# ttl_logic_mech.net
KiCad netlist of a schematic drawn in Altium Designer
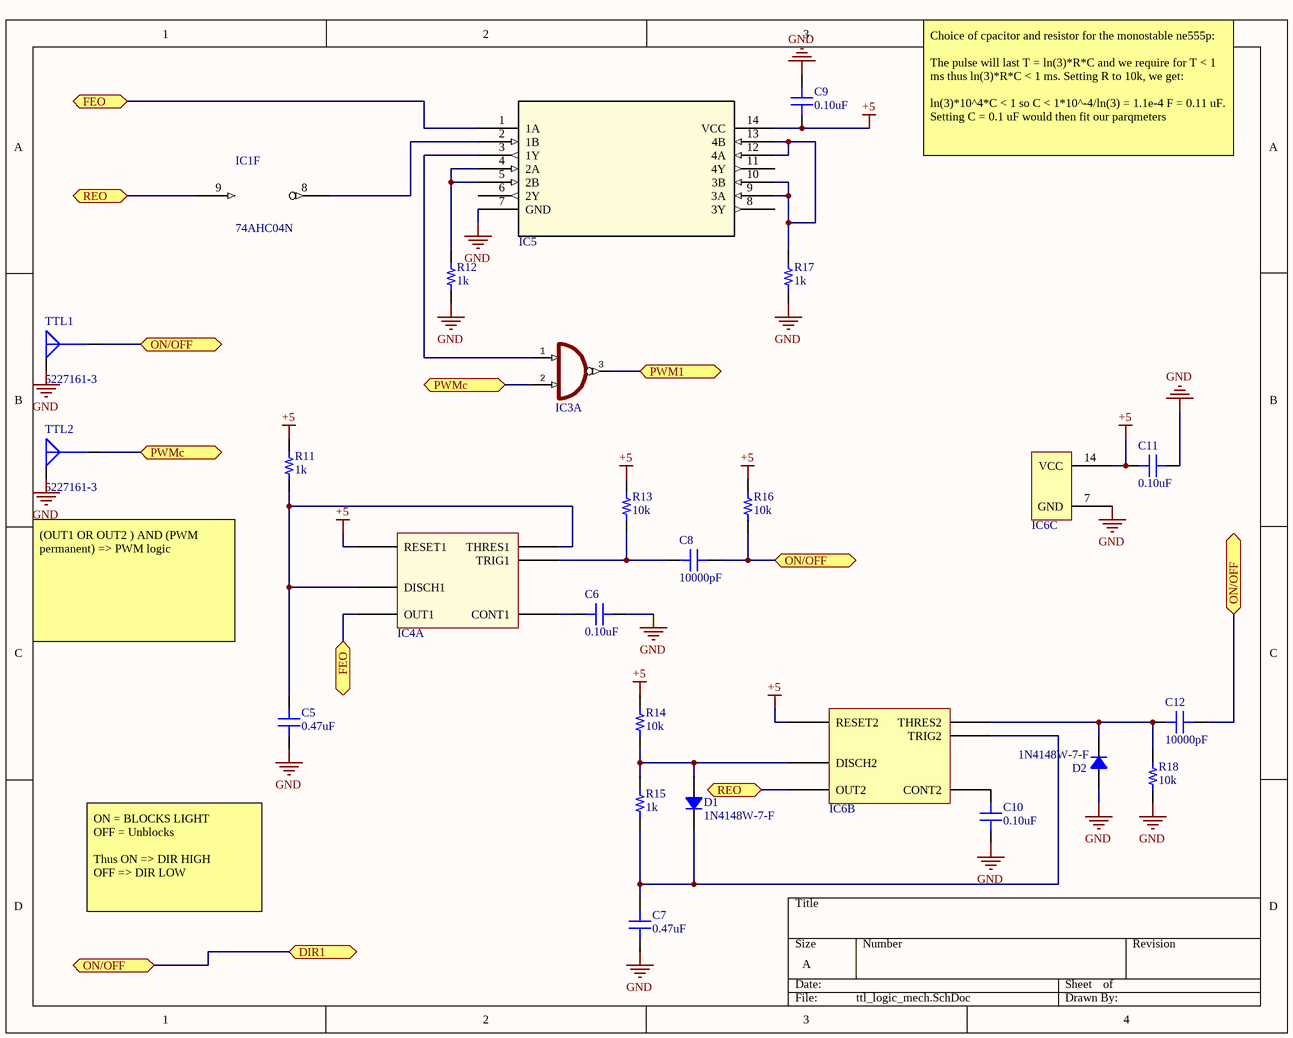
[diagram p0: ttl_logic_mech.SchDoc]

(export (version "E")
  (design (tool "Eeschema 10.0.6"))
  (components
    (comp (ref "C5")
      (value "0.47uF")
      (footprint "CAP 0805/2012")
      (description "CAP CER 0.47UF 16V X7R 0805")
      (fields (field (name "PART NUMBER") "C0805C474J4RACTU") (field (name "MANUFACTURER") "Kemet"))
      (libsource (lib "Celestial Library Database") (part "Capacitor"))
    )
    (comp (ref "C6")
      (value "0.10uF")
      (footprint "CAP 1206/3216 - 1.0MM")
      (description "CAP CER 0.1UF 16V X7R 1206")
      (fields (field (name "PART NUMBER") "C1206C104K4RACTU") (field (name "MANUFACTURER") "Kemet"))
      (libsource (lib "Celestial Library Database") (part "Capacitor"))
    )
    (comp (ref "C7")
      (value "0.47uF")
      (footprint "CAP 0805/2012")
      (description "CAP CER 0.47UF 16V X7R 0805")
      (fields (field (name "PART NUMBER") "C0805C474J4RACTU") (field (name "MANUFACTURER") "Kemet"))
      (libsource (lib "Celestial Library Database") (part "Capacitor"))
    )
    (comp (ref "C8")
      (value "10000pF")
      (footprint "CAP 0805/2012")
      (description "CAP CER 10000PF 25V X7R 0805")
      (fields (field (name "PART NUMBER") "C0805C103J3RACTU") (field (name "MANUFACTURER") "Kemet"))
      (libsource (lib "Celestial Library Database") (part "Capacitor"))
    )
    (comp (ref "C9")
      (value "0.10uF")
      (footprint "CAP 1206/3216 - 1.0MM")
      (description "CAP CER 0.1UF 16V X7R 1206")
      (fields (field (name "PART NUMBER") "C1206C104K4RACTU") (field (name "MANUFACTURER") "Kemet"))
      (libsource (lib "Celestial Library Database") (part "Capacitor"))
    )
    (comp (ref "C10")
      (value "0.10uF")
      (footprint "CAP 1206/3216 - 1.0MM")
      (description "CAP CER 0.1UF 16V X7R 1206")
      (fields (field (name "PART NUMBER") "C1206C104K4RACTU") (field (name "MANUFACTURER") "Kemet"))
      (libsource (lib "Celestial Library Database") (part "Capacitor"))
    )
    (comp (ref "C11")
      (value "0.10uF")
      (footprint "CAP 1206/3216 - 1.0MM")
      (description "CAP CER 0.1UF 16V X7R 1206")
      (fields (field (name "PART NUMBER") "C1206C104K4RACTU") (field (name "MANUFACTURER") "Kemet"))
      (libsource (lib "Celestial Library Database") (part "Capacitor"))
    )
    (comp (ref "C12")
      (value "10000pF")
      (footprint "CAP 0805/2012")
      (description "CAP CER 10000PF 25V X7R 0805")
      (fields (field (name "PART NUMBER") "C0805C103J3RACTU") (field (name "MANUFACTURER") "Kemet"))
      (libsource (lib "Celestial Library Database") (part "Capacitor"))
    )
    (comp (ref "D1")
      (value "1N4148W-7-F")
      (footprint "SOD-123")
      (description "DIODE GEN PURP 100V 300MA SOD123")
      (fields (field (name "MANUFACTURER") "Diodes Incorporated"))
      (libsource (lib "Celestial Library Database") (part "Diode"))
    )
    (comp (ref "D2")
      (value "1N4148W-7-F")
      (footprint "SOD-123")
      (description "DIODE GEN PURP 100V 300MA SOD123")
      (fields (field (name "MANUFACTURER") "Diodes Incorporated"))
      (libsource (lib "Celestial Library Database") (part "Diode"))
    )
    (comp (ref "IC1") (value "74AHC04N") (footprint "DIL14") (libsource (lib "74ac-logic") (part "74AHC04N")))
    (comp (ref "IC3")
      (value "~")
      (footprint "Atmel SO-14 14S1")
      (description "IC GATE AND 4CH 2-INP 14-SOIC")
      (fields (field (name "PART NUMBER") "SN74AC08D") (field (name "MANUFACTURER") "Texas Instruments"))
      (libsource (lib "Celestial Library Database") (part "74AC08N"))
    )
    (comp (ref "IC4")
      (value "NE556D")
      (footprint "Atmel SO-14 14S1")
      (description "2 ne555 timers in one soic 14")
      (fields (field (name "MANUFACTURER") "Texas Instruments"))
      (libsource (lib "Celestial Library Database") (part "NE556P"))
    )
    (comp (ref "IC5")
      (value "SN74LS86ADR")
      (footprint "Atmel SO-14 14S1")
      (description "IC GATE XOR 4CH 2-INP 14-SOIC")
      (fields (field (name "MANUFACTURER") "Texas Instruments"))
      (libsource (lib "Celestial Library Database") (part "SN74LS86ADR"))
    )
    (comp (ref "IC6")
      (value "NE556P")
      (footprint "DIP14")
      (fields (field (name "MANUFACTURER") "Texas Instruments"))
      (libsource (lib "Celestial Library Database") (part "NE556P"))
    )
    (comp (ref "R11")
      (value "1k")
      (footprint "RES 1206/3216")
      (description "RES SMD 1K OHM 0.05% 1/4W 1206")
      (fields
        (field (name "PART NUMBER") "ERA-8ARW102V")
        (field (name "MANUFACTURER") "Panasonic Electronic Components")
      )
      (libsource (lib "Celestial Library Database") (part "Resistor"))
    )
    (comp (ref "R12")
      (value "1k")
      (footprint "RES 1206/3216")
      (description "RES SMD 1K OHM 0.05% 1/4W 1206")
      (fields
        (field (name "PART NUMBER") "ERA-8ARW102V")
        (field (name "MANUFACTURER") "Panasonic Electronic Components")
      )
      (libsource (lib "Celestial Library Database") (part "Resistor"))
    )
    (comp (ref "R13")
      (value "10k")
      (footprint "RES 1206/3216")
      (description "RES SMD 10K OHM 5% 1/4W 1206")
      (fields
        (field (name "PART NUMBER") "ERJ-8GEYJ103V")
        (field (name "MANUFACTURER") "Panasonic Electronic Components")
      )
      (libsource (lib "Celestial Library Database") (part "Resistor"))
    )
    (comp (ref "R14")
      (value "10k")
      (footprint "RES 1206/3216")
      (description "RES SMD 10K OHM 5% 1/4W 1206")
      (fields
        (field (name "PART NUMBER") "ERJ-8GEYJ103V")
        (field (name "MANUFACTURER") "Panasonic Electronic Components")
      )
      (libsource (lib "Celestial Library Database") (part "Resistor"))
    )
    (comp (ref "R15")
      (value "1k")
      (footprint "RES 1206/3216")
      (description "RES SMD 1K OHM 0.05% 1/4W 1206")
      (fields
        (field (name "PART NUMBER") "ERA-8ARW102V")
        (field (name "MANUFACTURER") "Panasonic Electronic Components")
      )
      (libsource (lib "Celestial Library Database") (part "Resistor"))
    )
    (comp (ref "R16")
      (value "10k")
      (footprint "RES 1206/3216")
      (description "RES SMD 10K OHM 5% 1/4W 1206")
      (fields
        (field (name "PART NUMBER") "ERJ-8GEYJ103V")
        (field (name "MANUFACTURER") "Panasonic Electronic Components")
      )
      (libsource (lib "Celestial Library Database") (part "Resistor"))
    )
    (comp (ref "R17")
      (value "1k")
      (footprint "RES 1206/3216")
      (description "RES SMD 1K OHM 0.05% 1/4W 1206")
      (fields
        (field (name "PART NUMBER") "ERA-8ARW102V")
        (field (name "MANUFACTURER") "Panasonic Electronic Components")
      )
      (libsource (lib "Celestial Library Database") (part "Resistor"))
    )
    (comp (ref "R18")
      (value "10k")
      (footprint "RES 1206/3216")
      (description "RES SMD 10K OHM 5% 1/4W 1206")
      (fields
        (field (name "PART NUMBER") "ERJ-8GEYJ103V")
        (field (name "MANUFACTURER") "Panasonic Electronic Components")
      )
      (libsource (lib "Celestial Library Database") (part "Resistor"))
    )
    (comp (ref "TTL1")
      (value "5227161-3")
      (footprint "5227161-3")
      (description "CONN BNC JACK R/A 50 OHM PCB")
      (fields (field (name "MANUFACTURER") "TE Connectivity AMP Connectors"))
      (libsource (lib "Celestial Library Database") (part "RF Connector - SMA"))
    )
    (comp (ref "TTL2")
      (value "5227161-3")
      (footprint "5227161-3")
      (description "CONN BNC JACK R/A 50 OHM PCB")
      (fields (field (name "MANUFACTURER") "TE Connectivity AMP Connectors"))
      (libsource (lib "Celestial Library Database") (part "RF Connector - SMA"))
    )
  )
  (nets
    (net (code "1") (name "+5") (class "Default")
      (node (ref "C11") (pin "2") (pinfunction "2_2") (pintype "passive"))
      (node (ref "C9") (pin "2") (pinfunction "2_2") (pintype "passive"))
      (node (ref "IC4") (pin "4") (pinfunction "RESET1_4") (pintype "passive"))
      (node (ref "IC5") (pin "14") (pinfunction "VCC_14") (pintype "power_in"))
      (node (ref "IC6") (pin "10") (pinfunction "RESET2_10") (pintype "passive"))
      (node (ref "IC6") (pin "14") (pinfunction "VCC_14") (pintype "passive"))
      (node (ref "R11") (pin "2") (pinfunction "2_2") (pintype "passive"))
      (node (ref "R13") (pin "2") (pinfunction "2_2") (pintype "passive"))
      (node (ref "R14") (pin "2") (pinfunction "2_2") (pintype "passive"))
      (node (ref "R16") (pin "2") (pinfunction "2_2") (pintype "passive"))
    )
    (net (code "2") (name "/DIR1") (class "Default")
      (node (ref "C12") (pin "2") (pinfunction "2_2") (pintype "passive"))
      (node (ref "C8") (pin "2") (pinfunction "2_2") (pintype "passive"))
      (node (ref "R16") (pin "1") (pinfunction "1_1") (pintype "passive"))
      (node (ref "TTL1") (pin "S") (pinfunction "S_S") (pintype "passive"))
    )
    (net (code "3") (name "/FEO") (class "Default")
      (node (ref "IC4") (pin "5") (pinfunction "OUT1_5") (pintype "passive"))
      (node (ref "IC5") (pin "1") (pinfunction "1A_1") (pintype "power_in"))
    )
    (net (code "4") (name "/PWM1") (class "Default")
      (node (ref "IC3") (pin "3") (pinfunction "O_3") (pintype "output"))
    )
    (net (code "5") (name "/PWMc") (class "Default")
      (node (ref "IC3") (pin "2") (pinfunction "I1_2") (pintype "input"))
      (node (ref "TTL2") (pin "S") (pinfunction "S_S") (pintype "passive"))
    )
    (net (code "6") (name "/REO") (class "Default")
      (node (ref "IC1") (pin "9") (pinfunction "I0_9") (pintype "input"))
      (node (ref "IC6") (pin "9") (pinfunction "OUT2_9") (pintype "passive"))
    )
    (net (code "7") (name "GND") (class "Default")
      (node (ref "C10") (pin "2") (pinfunction "2_2") (pintype "passive"))
      (node (ref "C11") (pin "1") (pinfunction "1_1") (pintype "passive"))
      (node (ref "C5") (pin "1") (pinfunction "1_1") (pintype "passive"))
      (node (ref "C6") (pin "1") (pinfunction "1_1") (pintype "passive"))
      (node (ref "C7") (pin "1") (pinfunction "1_1") (pintype "passive"))
      (node (ref "C9") (pin "1") (pinfunction "1_1") (pintype "passive"))
      (node (ref "D2") (pin "1") (pinfunction "1_1") (pintype "passive"))
      (node (ref "IC5") (pin "7") (pinfunction "GND_7") (pintype "power_in"))
      (node (ref "IC6") (pin "7") (pinfunction "GND_7") (pintype "passive"))
      (node (ref "R12") (pin "1") (pinfunction "1_1") (pintype "passive"))
      (node (ref "R17") (pin "1") (pinfunction "1_1") (pintype "passive"))
      (node (ref "R18") (pin "1") (pinfunction "1_1") (pintype "passive"))
      (node (ref "TTL1") (pin "G") (pinfunction "G_G") (pintype "passive"))
      (node (ref "TTL2") (pin "G") (pinfunction "G_G") (pintype "passive"))
    )
    (net (code "8") (name "Net-(IC1F-O0)") (class "Default")
      (node (ref "IC1") (pin "8") (pinfunction "O0_8") (pintype "output"))
      (node (ref "IC5") (pin "2") (pinfunction "1B_2") (pintype "input"))
    )
    (net (code "9") (name "Net-(IC3A-I0)") (class "Default")
      (node (ref "IC3") (pin "1") (pinfunction "I0_1") (pintype "input"))
      (node (ref "IC5") (pin "3") (pinfunction "1Y_3") (pintype "output"))
    )
    (net (code "10") (name "Net-(IC4A-CONT1)") (class "Default")
      (node (ref "C6") (pin "2") (pinfunction "2_2") (pintype "passive"))
      (node (ref "IC4") (pin "3") (pinfunction "CONT1_3") (pintype "passive"))
    )
    (net (code "11") (name "Net-(IC4A-DISCH1)") (class "Default")
      (node (ref "C5") (pin "2") (pinfunction "2_2") (pintype "passive"))
      (node (ref "IC4") (pin "1") (pinfunction "DISCH1_1") (pintype "passive"))
      (node (ref "IC4") (pin "2") (pinfunction "THRES1_2") (pintype "passive"))
      (node (ref "R11") (pin "1") (pinfunction "1_1") (pintype "passive"))
    )
    (net (code "12") (name "Net-(IC4A-TRIG1)") (class "Default")
      (node (ref "C8") (pin "1") (pinfunction "1_1") (pintype "passive"))
      (node (ref "IC4") (pin "6") (pinfunction "TRIG1_6") (pintype "passive"))
      (node (ref "R13") (pin "1") (pinfunction "1_1") (pintype "passive"))
    )
    (net (code "13") (name "Net-(IC5-2A)") (class "Default")
      (node (ref "IC5") (pin "4") (pinfunction "2A_4") (pintype "input"))
      (node (ref "IC5") (pin "5") (pinfunction "2B_5") (pintype "input"))
      (node (ref "R12") (pin "2") (pinfunction "2_2") (pintype "passive"))
    )
    (net (code "14") (name "Net-(IC5-3A)") (class "Default")
      (node (ref "IC5") (pin "10") (pinfunction "3B_10") (pintype "input"))
      (node (ref "IC5") (pin "12") (pinfunction "4A_12") (pintype "input"))
      (node (ref "IC5") (pin "13") (pinfunction "4B_13") (pintype "input"))
      (node (ref "IC5") (pin "9") (pinfunction "3A_9") (pintype "input"))
      (node (ref "R17") (pin "2") (pinfunction "2_2") (pintype "passive"))
    )
    (net (code "15") (name "Net-(IC6B-CONT2)") (class "Default")
      (node (ref "C10") (pin "1") (pinfunction "1_1") (pintype "passive"))
      (node (ref "IC6") (pin "11") (pinfunction "CONT2_11") (pintype "passive"))
    )
    (net (code "16") (name "Net-(IC6B-DISCH2)") (class "Default")
      (node (ref "D1") (pin "1") (pinfunction "1_1") (pintype "passive"))
      (node (ref "IC6") (pin "13") (pinfunction "DISCH2_13") (pintype "passive"))
      (node (ref "R14") (pin "1") (pinfunction "1_1") (pintype "passive"))
      (node (ref "R15") (pin "2") (pinfunction "2_2") (pintype "passive"))
    )
    (net (code "17") (name "Net-(IC6B-THRES2)") (class "Default")
      (node (ref "C12") (pin "1") (pinfunction "1_1") (pintype "passive"))
      (node (ref "D2") (pin "2") (pinfunction "2_2") (pintype "passive"))
      (node (ref "IC6") (pin "12") (pinfunction "THRES2_12") (pintype "passive"))
      (node (ref "R18") (pin "2") (pinfunction "2_2") (pintype "passive"))
    )
    (net (code "18") (name "Net-(IC6B-TRIG2)") (class "Default")
      (node (ref "C7") (pin "2") (pinfunction "2_2") (pintype "passive"))
      (node (ref "D1") (pin "2") (pinfunction "2_2") (pintype "passive"))
      (node (ref "IC6") (pin "8") (pinfunction "TRIG2_8") (pintype "passive"))
      (node (ref "R15") (pin "1") (pinfunction "1_1") (pintype "passive"))
    )
    (net (code "19") (name "unconnected-(IC5-2Y-Pad6)") (class "Default")
      (node (ref "IC5") (pin "6") (pinfunction "2Y_6") (pintype "output"))
    )
    (net (code "20") (name "unconnected-(IC5-3Y-Pad8)") (class "Default")
      (node (ref "IC5") (pin "8") (pinfunction "3Y_8") (pintype "output"))
    )
    (net (code "21") (name "unconnected-(IC5-4Y-Pad11)") (class "Default")
      (node (ref "IC5") (pin "11") (pinfunction "4Y_11") (pintype "output"))
    )
  )
)
